# WATSH2.net
KiCad netlist of a schematic drawn in Altium Designer
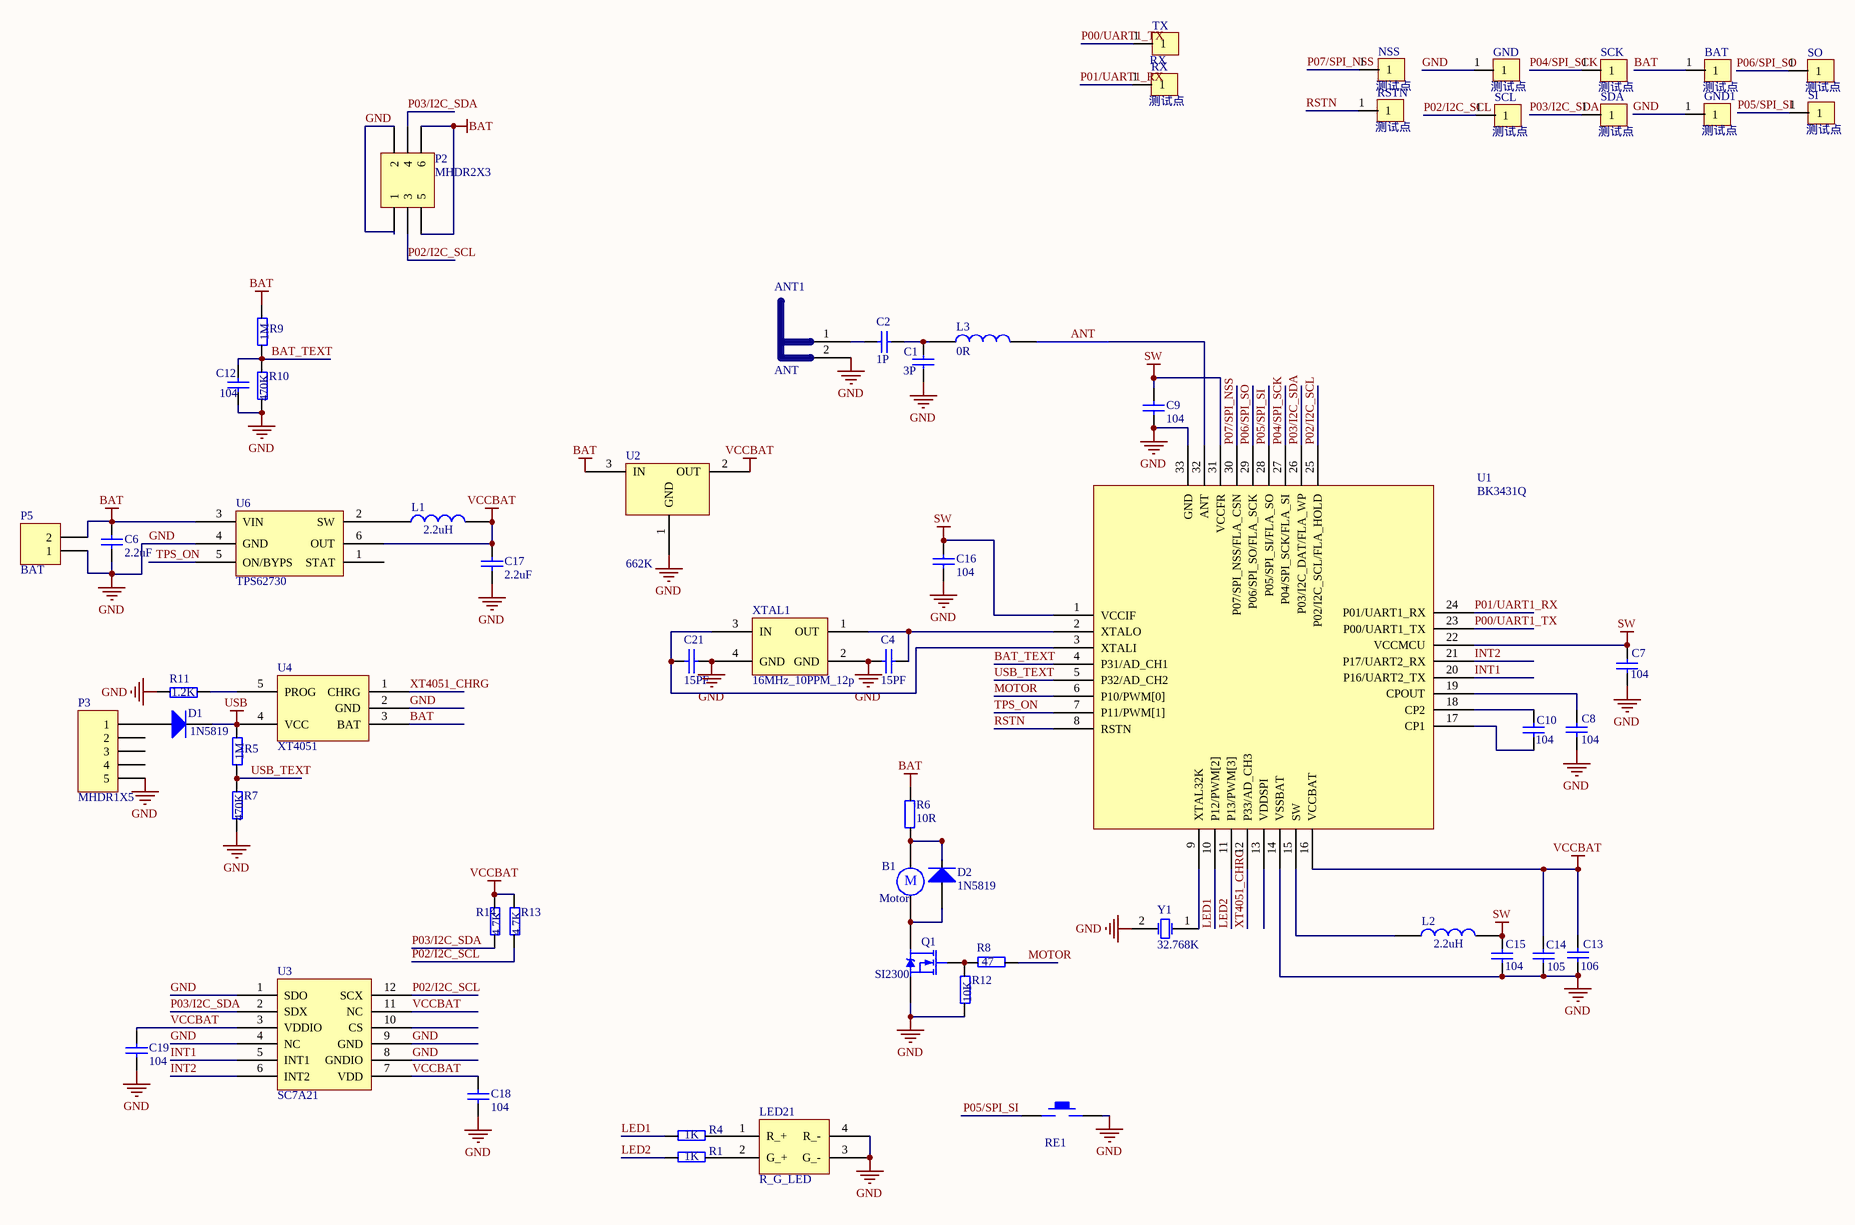
[diagram p0: WATSH2.SchDoc]

(export (version "E")
  (design (tool "Eeschema 10.0.6"))
  (components
    (comp (ref "ANT1") (value "ANT") (footprint "3216") (libsource (lib "元件") (part "ANT")))
    (comp (ref "B1")
      (value "Motor")
      (footprint "MODER")
      (description "Motor, General Kind")
      (fields (field (name "PUBLISHER") "Altium Limited"))
      (libsource (lib "Miscellaneous Devices") (part "Motor"))
    )
    (comp (ref "BAT") (value "测试点") (footprint "TEXT_POINT") (libsource (lib "元件") (part "测试点")))
    (comp (ref "C1")
      (value "3P")
      (footprint "0402_C")
      (description "Capacitor")
      (fields (field (name "PUBLISHER") "Altium Limited"))
      (libsource (lib "Miscellaneous Devices") (part "Cap"))
    )
    (comp (ref "C2")
      (value "1P")
      (footprint "0402_C")
      (description "Capacitor")
      (fields (field (name "PUBLISHER") "Altium Limited"))
      (libsource (lib "Miscellaneous Devices") (part "Cap"))
    )
    (comp (ref "C4")
      (value "15PF")
      (footprint "0402_C")
      (description "Capacitor")
      (libsource (lib "元件") (part "CAP"))
    )
    (comp (ref "C6")
      (value "2.2uF")
      (footprint "0402_C")
      (description "Capacitor")
      (fields (field (name "PUBLISHER") "Altium Limited"))
      (libsource (lib "Miscellaneous Devices") (part "Cap"))
    )
    (comp (ref "C7")
      (value "104")
      (footprint "0402_C")
      (description "Capacitor")
      (fields (field (name "PUBLISHER") "Altium Limited"))
      (libsource (lib "Miscellaneous Devices") (part "Cap"))
    )
    (comp (ref "C8")
      (value "104")
      (footprint "0402_C")
      (description "Capacitor")
      (fields (field (name "PUBLISHER") "Altium Limited"))
      (libsource (lib "Miscellaneous Devices") (part "Cap"))
    )
    (comp (ref "C9")
      (value "104")
      (footprint "0402_C")
      (description "Capacitor")
      (fields (field (name "PUBLISHER") "Altium Limited"))
      (libsource (lib "Miscellaneous Devices") (part "Cap"))
    )
    (comp (ref "C10")
      (value "104")
      (footprint "0402_C")
      (description "Capacitor")
      (fields (field (name "PUBLISHER") "Altium Limited"))
      (libsource (lib "Miscellaneous Devices") (part "Cap"))
    )
    (comp (ref "C12")
      (value "104")
      (footprint "0402_C")
      (description "Capacitor")
      (fields (field (name "PUBLISHER") "Altium Limited"))
      (libsource (lib "Miscellaneous Devices") (part "Cap"))
    )
    (comp (ref "C13")
      (value "106")
      (footprint "0402_C")
      (description "Capacitor")
      (fields (field (name "PUBLISHER") "Altium Limited"))
      (libsource (lib "Miscellaneous Devices") (part "Cap"))
    )
    (comp (ref "C14")
      (value "105")
      (footprint "0402_C")
      (description "Capacitor")
      (fields (field (name "PUBLISHER") "Altium Limited"))
      (libsource (lib "Miscellaneous Devices") (part "Cap"))
    )
    (comp (ref "C15")
      (value "104")
      (footprint "0402_C")
      (description "Capacitor")
      (fields (field (name "PUBLISHER") "Altium Limited"))
      (libsource (lib "Miscellaneous Devices") (part "Cap"))
    )
    (comp (ref "C16")
      (value "104")
      (footprint "0402_C")
      (description "Capacitor")
      (fields (field (name "PUBLISHER") "Altium Limited"))
      (libsource (lib "Miscellaneous Devices") (part "Cap"))
    )
    (comp (ref "C17")
      (value "2.2uF")
      (footprint "0402_C")
      (description "Capacitor")
      (fields (field (name "PUBLISHER") "Altium Limited"))
      (libsource (lib "Miscellaneous Devices") (part "Cap"))
    )
    (comp (ref "C18")
      (value "104")
      (footprint "0402_C")
      (description "Capacitor")
      (fields (field (name "PUBLISHER") "Altium Limited"))
      (libsource (lib "Miscellaneous Devices") (part "Cap"))
    )
    (comp (ref "C19")
      (value "104")
      (footprint "0402_C")
      (description "Capacitor")
      (fields (field (name "PUBLISHER") "Altium Limited"))
      (libsource (lib "Miscellaneous Devices") (part "Cap"))
    )
    (comp (ref "C21")
      (value "15PF")
      (footprint "0402_C")
      (description "Capacitor")
      (libsource (lib "元件") (part "CAP"))
    )
    (comp (ref "D1")
      (value "1N5819")
      (footprint "SOD-323")
      (description "1 Amp General Purpose Rectifier")
      (fields (field (name "PUBLISHER") "Altium Limited"))
      (libsource (lib "Miscellaneous Devices") (part "Diode 1N4001"))
    )
    (comp (ref "D2")
      (value "1N5819")
      (footprint "SOD-523")
      (description "1 Amp General Purpose Rectifier")
      (fields (field (name "PUBLISHER") "Altium Limited"))
      (libsource (lib "Miscellaneous Devices") (part "Diode 1N4001"))
    )
    (comp (ref "GND") (value "测试点") (footprint "TEXT_POINT") (libsource (lib "元件") (part "测试点")))
    (comp (ref "GND1") (value "测试点") (footprint "TEXT_POINT") (libsource (lib "元件") (part "测试点")))
    (comp (ref "L1") (value "2.2uH") (footprint "0603p") (libsource (lib "*") (part "INDUCTOR")))
    (comp (ref "L2") (value "2.2uH") (footprint "0603p") (libsource (lib "*") (part "INDUCTOR")))
    (comp (ref "L3") (value "0R") (footprint "0402_L") (libsource (lib "*") (part "INDUCTOR")))
    (comp (ref "LED21") (value "R_G_LED") (footprint "0603_R_G_LED") (libsource (lib "元件") (part "R_G_LED")))
    (comp (ref "NSS") (value "测试点") (footprint "TEXT_POINT") (libsource (lib "元件") (part "测试点")))
    (comp (ref "P2")
      (value "MHDR2X3")
      (footprint "AXF-6A-M")
      (description "Header, 3-Pin, Dual row")
      (fields (field (name "PUBLISHER") "Altium Limited"))
      (libsource (lib "Miscellaneous Connectors") (part "MHDR2X3"))
    )
    (comp (ref "P3")
      (value "MHDR1X5")
      (footprint "MINI_USB_2P")
      (description "Header, 5-Pin")
      (fields (field (name "PUBLISHER") "Altium Limited"))
      (libsource (lib "Miscellaneous Connectors") (part "MHDR1X5"))
    )
    (comp (ref "P5")
      (value "BAT")
      (footprint "HDR1X2")
      (description "Header, 2-Pin")
      (fields (field (name "PUBLISHER") "Altium Limited"))
      (libsource (lib "Miscellaneous Connectors") (part "Header 2"))
    )
    (comp (ref "Q1")
      (value "SI2300")
      (footprint "SOT-523")
      (description "N-Channel MOSFET")
      (fields (field (name "PUBLISHER") "Altium Limited"))
      (libsource (lib "Fszhang") (part "MOSFET-N"))
    )
    (comp (ref "R1") (value "1K") (footprint "0402_R") (libsource (lib "Explorer STM32F407封装库") (part "R")))
    (comp (ref "R4")
      (value "1K")
      (footprint "自画库1:0402_R")
      (libsource (lib "Explorer STM32F407封装库") (part "R"))
    )
    (comp (ref "R5") (value "1M") (footprint "0402_R") (libsource (lib "Explorer STM32F407封装库") (part "R")))
    (comp (ref "R6") (value "10R") (footprint "0603_R") (libsource (lib "Explorer STM32F407封装库") (part "R")))
    (comp (ref "R7") (value "470K") (footprint "0402_R") (libsource (lib "Explorer STM32F407封装库") (part "R")))
    (comp (ref "R8") (value "47") (footprint "0603_R") (libsource (lib "Explorer STM32F407封装库") (part "R")))
    (comp (ref "R9") (value "1M") (footprint "0402_R") (libsource (lib "Explorer STM32F407封装库") (part "R")))
    (comp (ref "R10")
      (value "470K")
      (footprint "0402_R")
      (libsource (lib "Explorer STM32F407封装库") (part "R"))
    )
    (comp (ref "R11")
      (value "1.2K")
      (footprint "0402_R")
      (libsource (lib "Explorer STM32F407封装库") (part "R"))
    )
    (comp (ref "R12")
      (value "10K")
      (footprint "自画库1:0402_R")
      (libsource (lib "Explorer STM32F407封装库") (part "R"))
    )
    (comp (ref "R13")
      (value "4.7K")
      (footprint "自画库1:0402_R")
      (libsource (lib "Explorer STM32F407封装库") (part "R"))
    )
    (comp (ref "R14")
      (value "4.7K")
      (footprint "自画库1:0402_R")
      (libsource (lib "Explorer STM32F407封装库") (part "R"))
    )
    (comp (ref "RE1")
      (value "KEY_M")
      (footprint "轻触开关 2x4")
      (libsource (lib "Explorer STM32F407封装库") (part "KEY_M"))
    )
    (comp (ref "RSTN") (value "测试点") (footprint "TEXT_POINT") (libsource (lib "元件") (part "测试点")))
    (comp (ref "RX") (value "测试点") (footprint "TEXT_POINT") (libsource (lib "元件") (part "测试点")))
    (comp (ref "SCK") (value "测试点") (footprint "TEXT_POINT") (libsource (lib "元件") (part "测试点")))
    (comp (ref "SCL") (value "测试点") (footprint "TEXT_POINT") (libsource (lib "元件") (part "测试点")))
    (comp (ref "SDA") (value "测试点") (footprint "TEXT_POINT") (libsource (lib "元件") (part "测试点")))
    (comp (ref "SI") (value "测试点") (footprint "TEXT_POINT") (libsource (lib "元件") (part "测试点")))
    (comp (ref "SO") (value "测试点") (footprint "TEXT_POINT") (libsource (lib "元件") (part "测试点")))
    (comp (ref "TX") (value "RX") (footprint "TEXT_POINT") (libsource (lib "元件") (part "测试点")))
    (comp (ref "U1") (value "BK3431Q") (footprint "QFN32") (libsource (lib "元件") (part "BK3431Q")))
    (comp (ref "U2") (value "662K") (footprint "SOT-23") (libsource (lib "元件") (part "662K")))
    (comp (ref "U3") (value "SC7A21") (footprint "LGA-12-2*2*1") (libsource (lib "元件") (part "SC7A21")))
    (comp (ref "U4") (value "XT4051") (footprint "SOT-23-5L") (libsource (lib "元件") (part "XT4051")))
    (comp (ref "U6") (value "TPS62730") (footprint "R-PUSON-N6") (libsource (lib "元件") (part "TPS62730")))
    (comp (ref "XTAL1") (value "16MHz_10PPM_12p") (footprint "晶振2*2.6") (libsource (lib "元件") (part "晶振")))
    (comp (ref "Y1")
      (value "32.768K")
      (footprint "晶振1.5*3.2")
      (description "Crystal Oscillator")
      (fields (field (name "PUBLISHER") "Altium Limited"))
      (libsource (lib "Explorer STM32F407封装库") (part "XTAL_1"))
    )
  )
  (nets
    (net (code "1") (name "/ANT") (class "Default")
      (node (ref "L3") (pin "1") (pinfunction "1_1") (pintype "passive"))
      (node (ref "U1") (pin "32") (pinfunction "ANT_32") (pintype "passive"))
    )
    (net (code "2") (name "/BAT_TEXT") (class "Default")
      (node (ref "C12") (pin "2") (pinfunction "2_2") (pintype "passive"))
      (node (ref "R10") (pin "2") (pintype "passive"))
      (node (ref "R9") (pin "1") (pintype "passive"))
      (node (ref "U1") (pin "4") (pinfunction "P31/AD_CH1_4") (pintype "passive"))
    )
    (net (code "3") (name "/INT1") (class "Default")
      (node (ref "U1") (pin "20") (pinfunction "P16/UART2_TX_20") (pintype "passive"))
      (node (ref "U3") (pin "5") (pinfunction "INT1_5") (pintype "passive"))
    )
    (net (code "4") (name "/INT2") (class "Default")
      (node (ref "U1") (pin "21") (pinfunction "P17/UART2_RX_21") (pintype "passive"))
      (node (ref "U3") (pin "6") (pinfunction "INT2_6") (pintype "passive"))
    )
    (net (code "5") (name "/LED1") (class "Default")
      (node (ref "R4") (pin "2") (pintype "passive"))
      (node (ref "U1") (pin "10") (pinfunction "P12/PWM[2]_10") (pintype "passive"))
    )
    (net (code "6") (name "/LED2") (class "Default")
      (node (ref "R1") (pin "2") (pintype "passive"))
      (node (ref "U1") (pin "11") (pinfunction "P13/PWM[3]_11") (pintype "passive"))
    )
    (net (code "7") (name "/MOTOR") (class "Default")
      (node (ref "R8") (pin "1") (pintype "passive"))
      (node (ref "U1") (pin "6") (pinfunction "P10/PWM[0]_6") (pintype "passive"))
    )
    (net (code "8") (name "/P00{slash}UART1_TX") (class "Default")
      (node (ref "TX") (pin "1") (pinfunction "1_1") (pintype "passive"))
      (node (ref "U1") (pin "23") (pinfunction "P00/UART1_TX_23") (pintype "passive"))
    )
    (net (code "9") (name "/P01{slash}UART1_RX") (class "Default")
      (node (ref "RX") (pin "1") (pinfunction "1_1") (pintype "passive"))
      (node (ref "U1") (pin "24") (pinfunction "P01/UART1_RX_24") (pintype "passive"))
    )
    (net (code "10") (name "/P02{slash}I2C_SCL") (class "Default")
      (node (ref "P2") (pin "3") (pinfunction "3_3") (pintype "passive"))
      (node (ref "R13") (pin "1") (pintype "passive"))
      (node (ref "SCL") (pin "1") (pinfunction "1_1") (pintype "passive"))
      (node (ref "U1") (pin "25") (pinfunction "P02/I2C_SCL/FLA_HOLD_25") (pintype "passive"))
      (node (ref "U3") (pin "12") (pinfunction "SCX_12") (pintype "passive"))
    )
    (net (code "11") (name "/P03{slash}I2C_SDA") (class "Default")
      (node (ref "P2") (pin "4") (pinfunction "4_4") (pintype "passive"))
      (node (ref "R14") (pin "1") (pintype "passive"))
      (node (ref "SDA") (pin "1") (pinfunction "1_1") (pintype "passive"))
      (node (ref "U1") (pin "26") (pinfunction "P03/I2C_DAT/FLA_WP_26") (pintype "passive"))
      (node (ref "U3") (pin "2") (pinfunction "SDX_2") (pintype "passive"))
    )
    (net (code "12") (name "/P04{slash}SPI_SCK") (class "Default")
      (node (ref "SCK") (pin "1") (pinfunction "1_1") (pintype "passive"))
      (node (ref "U1") (pin "27") (pinfunction "P04/SPI_SCK/FLA_SI_27") (pintype "passive"))
    )
    (net (code "13") (name "/P05{slash}SPI_SI") (class "Default")
      (node (ref "RE1") (pin "1") (pinfunction "1_1") (pintype "passive"))
      (node (ref "SI") (pin "1") (pinfunction "1_1") (pintype "passive"))
      (node (ref "U1") (pin "28") (pinfunction "P05/SPI_SI/FLA_SO_28") (pintype "passive"))
    )
    (net (code "14") (name "/P06{slash}SPI_SO") (class "Default")
      (node (ref "SO") (pin "1") (pinfunction "1_1") (pintype "passive"))
      (node (ref "U1") (pin "29") (pinfunction "P06/SPI_SO/FLA_SCK_29") (pintype "passive"))
    )
    (net (code "15") (name "/P07{slash}SPI_NSS") (class "Default")
      (node (ref "NSS") (pin "1") (pinfunction "1_1") (pintype "passive"))
      (node (ref "U1") (pin "30") (pinfunction "P07/SPI_NSS/FLA_CSN_30") (pintype "passive"))
    )
    (net (code "16") (name "/RSTN") (class "Default")
      (node (ref "RSTN") (pin "1") (pinfunction "1_1") (pintype "passive"))
      (node (ref "U1") (pin "8") (pinfunction "RSTN_8") (pintype "passive"))
    )
    (net (code "17") (name "/TPS_ON") (class "Default")
      (node (ref "U1") (pin "7") (pinfunction "P11/PWM[1]_7") (pintype "passive"))
      (node (ref "U6") (pin "5") (pinfunction "ON/BYPS_5") (pintype "passive"))
    )
    (net (code "18") (name "/USB_TEXT") (class "Default")
      (node (ref "R5") (pin "1") (pintype "passive"))
      (node (ref "R7") (pin "2") (pintype "passive"))
      (node (ref "U1") (pin "5") (pinfunction "P32/AD_CH2_5") (pintype "passive"))
    )
    (net (code "19") (name "/XT4051_CHRG") (class "Default")
      (node (ref "U1") (pin "12") (pinfunction "P33/AD_CH3_12") (pintype "passive"))
      (node (ref "U4") (pin "1") (pinfunction "CHRG_1") (pintype "passive"))
    )
    (net (code "20") (name "BAT") (class "Default")
      (node (ref "BAT") (pin "1") (pinfunction "1_1") (pintype "passive"))
      (node (ref "C6") (pin "2") (pinfunction "2_2") (pintype "passive"))
      (node (ref "P2") (pin "5") (pinfunction "5_5") (pintype "passive"))
      (node (ref "P2") (pin "6") (pinfunction "6_6") (pintype "passive"))
      (node (ref "P5") (pin "2") (pinfunction "2_2") (pintype "passive"))
      (node (ref "R6") (pin "1") (pintype "passive"))
      (node (ref "R9") (pin "2") (pintype "passive"))
      (node (ref "U2") (pin "3") (pinfunction "IN_3") (pintype "passive"))
      (node (ref "U4") (pin "3") (pinfunction "BAT_3") (pintype "passive"))
      (node (ref "U6") (pin "3") (pinfunction "VIN_3") (pintype "passive"))
    )
    (net (code "21") (name "GND") (class "Default")
      (node (ref "ANT1") (pin "2") (pinfunction "GND_2") (pintype "passive"))
      (node (ref "C1") (pin "1") (pinfunction "1_1") (pintype "passive"))
      (node (ref "C12") (pin "1") (pinfunction "1_1") (pintype "passive"))
      (node (ref "C13") (pin "1") (pinfunction "1_1") (pintype "passive"))
      (node (ref "C14") (pin "1") (pinfunction "1_1") (pintype "passive"))
      (node (ref "C15") (pin "1") (pinfunction "1_1") (pintype "passive"))
      (node (ref "C16") (pin "1") (pinfunction "1_1") (pintype "passive"))
      (node (ref "C17") (pin "1") (pinfunction "1_1") (pintype "passive"))
      (node (ref "C18") (pin "2") (pinfunction "2_2") (pintype "passive"))
      (node (ref "C19") (pin "2") (pinfunction "2_2") (pintype "passive"))
      (node (ref "C21") (pin "2") (pinfunction "2_2") (pintype "passive"))
      (node (ref "C4") (pin "1") (pinfunction "1_1") (pintype "passive"))
      (node (ref "C6") (pin "1") (pinfunction "1_1") (pintype "passive"))
      (node (ref "C7") (pin "1") (pinfunction "1_1") (pintype "passive"))
      (node (ref "C8") (pin "1") (pinfunction "1_1") (pintype "passive"))
      (node (ref "C9") (pin "1") (pinfunction "1_1") (pintype "passive"))
      (node (ref "GND") (pin "1") (pinfunction "1_1") (pintype "passive"))
      (node (ref "GND1") (pin "1") (pinfunction "1_1") (pintype "passive"))
      (node (ref "LED21") (pin "3") (pinfunction "G_-_3") (pintype "passive"))
      (node (ref "LED21") (pin "4") (pinfunction "R_-_4") (pintype "passive"))
      (node (ref "P2") (pin "1") (pinfunction "1_1") (pintype "passive"))
      (node (ref "P2") (pin "2") (pinfunction "2_2") (pintype "passive"))
      (node (ref "P3") (pin "5") (pinfunction "5_5") (pintype "passive"))
      (node (ref "P5") (pin "1") (pinfunction "1_1") (pintype "passive"))
      (node (ref "Q1") (pin "S") (pinfunction "S_S") (pintype "passive"))
      (node (ref "R10") (pin "1") (pintype "passive"))
      (node (ref "R11") (pin "2") (pintype "passive"))
      (node (ref "R12") (pin "1") (pintype "passive"))
      (node (ref "R7") (pin "1") (pintype "passive"))
      (node (ref "RE1") (pin "2") (pinfunction "2_2") (pintype "passive"))
      (node (ref "U1") (pin "14") (pinfunction "VSSBAT_14") (pintype "passive"))
      (node (ref "U1") (pin "33") (pinfunction "GND_33") (pintype "passive"))
      (node (ref "U2") (pin "1") (pinfunction "GND_1") (pintype "passive"))
      (node (ref "U3") (pin "1") (pinfunction "SDO_1") (pintype "passive"))
      (node (ref "U3") (pin "4") (pinfunction "NC_4") (pintype "passive"))
      (node (ref "U3") (pin "8") (pinfunction "GNDIO_8") (pintype "passive"))
      (node (ref "U3") (pin "9") (pinfunction "GND_9") (pintype "passive"))
      (node (ref "U4") (pin "2") (pinfunction "GND_2") (pintype "passive"))
      (node (ref "U6") (pin "4") (pinfunction "GND_4") (pintype "passive"))
      (node (ref "XTAL1") (pin "2") (pinfunction "GND_2") (pintype "passive"))
      (node (ref "XTAL1") (pin "4") (pinfunction "GND_4") (pintype "passive"))
      (node (ref "Y1") (pin "2") (pinfunction "OSC2_2") (pintype "passive"))
    )
    (net (code "22") (name "Net-(ANT1-ANT)") (class "Default")
      (node (ref "ANT1") (pin "1") (pinfunction "ANT_1") (pintype "passive"))
      (node (ref "C2") (pin "1") (pinfunction "1_1") (pintype "passive"))
    )
    (net (code "23") (name "Net-(C1-Pad2)") (class "Default")
      (node (ref "C1") (pin "2") (pinfunction "2_2") (pintype "passive"))
      (node (ref "C2") (pin "2") (pinfunction "2_2") (pintype "passive"))
      (node (ref "L3") (pin "2") (pinfunction "2_2") (pintype "passive"))
    )
    (net (code "24") (name "Net-(D1-A)") (class "Default")
      (node (ref "D1") (pin "1") (pinfunction "A_1") (pintype "passive"))
      (node (ref "P3") (pin "1") (pinfunction "1_1") (pintype "passive"))
    )
    (net (code "25") (name "Net-(D2-A)") (class "Default")
      (node (ref "B1") (pin "2") (pinfunction "2_2") (pintype "passive"))
      (node (ref "D2") (pin "1") (pinfunction "A_1") (pintype "passive"))
      (node (ref "Q1") (pin "D") (pinfunction "D_D") (pintype "passive"))
    )
    (net (code "26") (name "Net-(D2-K)") (class "Default")
      (node (ref "B1") (pin "1") (pinfunction "1_1") (pintype "passive"))
      (node (ref "D2") (pin "2") (pinfunction "K_2") (pintype "passive"))
      (node (ref "R6") (pin "2") (pintype "passive"))
    )
    (net (code "27") (name "Net-(LED21-G_+)") (class "Default")
      (node (ref "LED21") (pin "2") (pinfunction "G_+_2") (pintype "passive"))
      (node (ref "R1") (pin "1") (pintype "passive"))
    )
    (net (code "28") (name "Net-(LED21-R_+)") (class "Default")
      (node (ref "LED21") (pin "1") (pinfunction "R_+_1") (pintype "passive"))
      (node (ref "R4") (pin "1") (pintype "passive"))
    )
    (net (code "29") (name "Net-(Q1-PadG)") (class "Default")
      (node (ref "Q1") (pin "G") (pinfunction "G_G") (pintype "passive"))
      (node (ref "R12") (pin "2") (pintype "passive"))
      (node (ref "R8") (pin "2") (pintype "passive"))
    )
    (net (code "30") (name "Net-(U1-CP1)") (class "Default")
      (node (ref "C10") (pin "1") (pinfunction "1_1") (pintype "passive"))
      (node (ref "U1") (pin "17") (pinfunction "CP1_17") (pintype "passive"))
    )
    (net (code "31") (name "Net-(U1-CP2)") (class "Default")
      (node (ref "C10") (pin "2") (pinfunction "2_2") (pintype "passive"))
      (node (ref "U1") (pin "18") (pinfunction "CP2_18") (pintype "passive"))
    )
    (net (code "32") (name "Net-(U1-CPOUT)") (class "Default")
      (node (ref "C8") (pin "2") (pinfunction "2_2") (pintype "passive"))
      (node (ref "U1") (pin "19") (pinfunction "CPOUT_19") (pintype "passive"))
    )
    (net (code "33") (name "Net-(U1-SW)") (class "Default")
      (node (ref "L2") (pin "2") (pinfunction "2_2") (pintype "passive"))
      (node (ref "U1") (pin "15") (pinfunction "SW_15") (pintype "passive"))
    )
    (net (code "34") (name "Net-(U1-XTAL32K)") (class "Default")
      (node (ref "U1") (pin "9") (pinfunction "XTAL32K_9") (pintype "passive"))
      (node (ref "Y1") (pin "1") (pinfunction "OSC1_1") (pintype "passive"))
    )
    (net (code "35") (name "Net-(U1-XTALI)") (class "Default")
      (node (ref "C21") (pin "1") (pinfunction "1_1") (pintype "passive"))
      (node (ref "U1") (pin "3") (pinfunction "XTALI_3") (pintype "passive"))
      (node (ref "XTAL1") (pin "3") (pinfunction "IN_3") (pintype "passive"))
    )
    (net (code "36") (name "Net-(U1-XTALO)") (class "Default")
      (node (ref "C4") (pin "2") (pinfunction "2_2") (pintype "passive"))
      (node (ref "U1") (pin "2") (pinfunction "XTALO_2") (pintype "passive"))
      (node (ref "XTAL1") (pin "1") (pinfunction "OUT_1") (pintype "passive"))
    )
    (net (code "37") (name "Net-(U4-PROG)") (class "Default")
      (node (ref "R11") (pin "1") (pintype "passive"))
      (node (ref "U4") (pin "5") (pinfunction "PROG_5") (pintype "passive"))
    )
    (net (code "38") (name "Net-(U6-SW)") (class "Default")
      (node (ref "L1") (pin "2") (pinfunction "2_2") (pintype "passive"))
      (node (ref "U6") (pin "2") (pinfunction "SW_2") (pintype "passive"))
    )
    (net (code "39") (name "SW") (class "Default")
      (node (ref "C15") (pin "2") (pinfunction "2_2") (pintype "passive"))
      (node (ref "C16") (pin "2") (pinfunction "2_2") (pintype "passive"))
      (node (ref "C7") (pin "2") (pinfunction "2_2") (pintype "passive"))
      (node (ref "C9") (pin "2") (pinfunction "2_2") (pintype "passive"))
      (node (ref "L2") (pin "1") (pinfunction "1_1") (pintype "passive"))
      (node (ref "U1") (pin "1") (pinfunction "VCCIF_1") (pintype "passive"))
      (node (ref "U1") (pin "22") (pinfunction "VCCMCU_22") (pintype "passive"))
      (node (ref "U1") (pin "31") (pinfunction "VCCFR_31") (pintype "passive"))
    )
    (net (code "40") (name "USB") (class "Default")
      (node (ref "D1") (pin "2") (pinfunction "K_2") (pintype "passive"))
      (node (ref "R5") (pin "2") (pintype "passive"))
      (node (ref "U4") (pin "4") (pinfunction "VCC_4") (pintype "passive"))
    )
    (net (code "41") (name "VCCBAT") (class "Default")
      (node (ref "C13") (pin "2") (pinfunction "2_2") (pintype "passive"))
      (node (ref "C14") (pin "2") (pinfunction "2_2") (pintype "passive"))
      (node (ref "C17") (pin "2") (pinfunction "2_2") (pintype "passive"))
      (node (ref "C18") (pin "1") (pinfunction "1_1") (pintype "passive"))
      (node (ref "C19") (pin "1") (pinfunction "1_1") (pintype "passive"))
      (node (ref "L1") (pin "1") (pinfunction "1_1") (pintype "passive"))
      (node (ref "R13") (pin "2") (pintype "passive"))
      (node (ref "R14") (pin "2") (pintype "passive"))
      (node (ref "U1") (pin "16") (pinfunction "VCCBAT_16") (pintype "passive"))
      (node (ref "U2") (pin "2") (pinfunction "OUT_2") (pintype "passive"))
      (node (ref "U3") (pin "11") (pinfunction "NC_11") (pintype "passive"))
      (node (ref "U3") (pin "3") (pinfunction "VDDIO_3") (pintype "passive"))
      (node (ref "U3") (pin "7") (pinfunction "VDD_7") (pintype "passive"))
      (node (ref "U6") (pin "6") (pinfunction "OUT_6") (pintype "passive"))
    )
    (net (code "42") (name "unconnected-(P3-Pad2)") (class "Default")
      (node (ref "P3") (pin "2") (pinfunction "2_2") (pintype "passive"))
    )
    (net (code "43") (name "unconnected-(P3-Pad3)") (class "Default")
      (node (ref "P3") (pin "3") (pinfunction "3_3") (pintype "passive"))
    )
    (net (code "44") (name "unconnected-(P3-Pad4)") (class "Default")
      (node (ref "P3") (pin "4") (pinfunction "4_4") (pintype "passive"))
    )
    (net (code "45") (name "unconnected-(U1-VDDSPI-Pad13)") (class "Default")
      (node (ref "U1") (pin "13") (pinfunction "VDDSPI_13") (pintype "passive"))
    )
    (net (code "46") (name "unconnected-(U3-CS-Pad10)") (class "Default")
      (node (ref "U3") (pin "10") (pinfunction "CS_10") (pintype "passive"))
    )
    (net (code "47") (name "unconnected-(U6-STAT-Pad1)") (class "Default")
      (node (ref "U6") (pin "1") (pinfunction "STAT_1") (pintype "passive"))
    )
  )
)
